# SolBin.net
KiCad netlist of a schematic drawn in Altium Designer
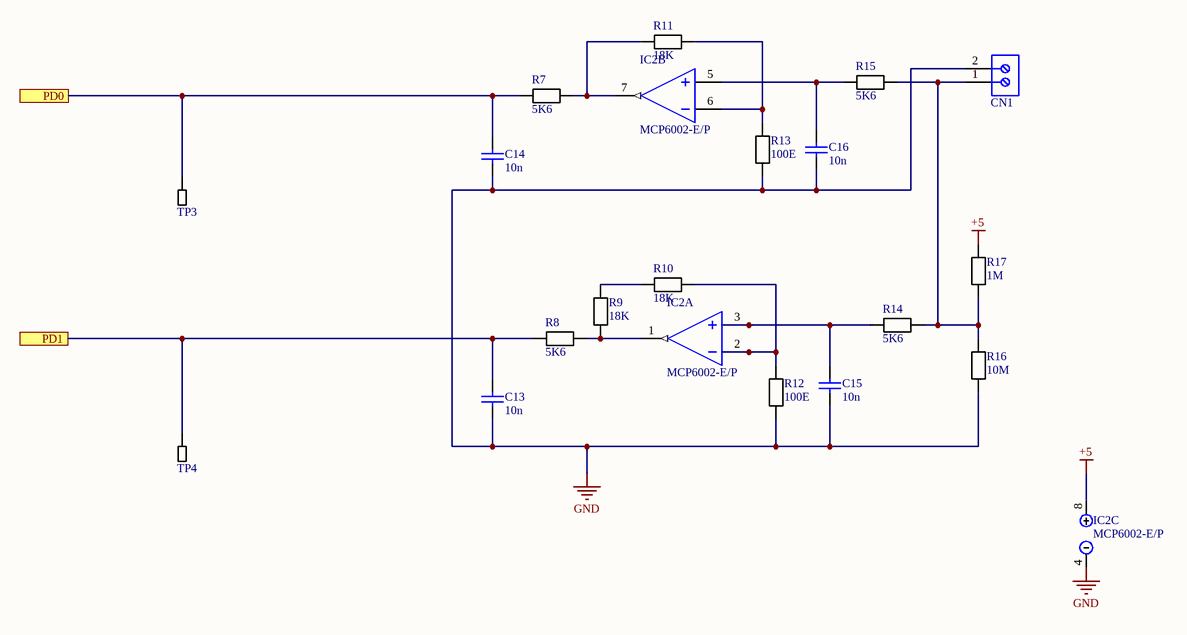
[diagram p0: SolBin.SchDoc]

(export (version "E")
  (design (tool "Eeschema 10.0.6"))
  (components
    (comp (ref "C13")
      (value "10n")
      (footprint "CAPA")
      (fields (field (name "PART NUMBER") "GRM1885C1H100JA01D") (field (name "MANUFACTURER") "Murata"))
      (libsource (lib "Schlib1") (part "Capasitor"))
    )
    (comp (ref "C14")
      (value "10n")
      (footprint "CAPA")
      (fields (field (name "PART NUMBER") "GRM1885C1H100JA01D") (field (name "MANUFACTURER") "Murata"))
      (libsource (lib "Schlib1") (part "Capasitor"))
    )
    (comp (ref "C15")
      (value "10n")
      (footprint "CAPA")
      (fields (field (name "PART NUMBER") "GRM1885C1H100JA01D") (field (name "MANUFACTURER") "Murata"))
      (libsource (lib "Schlib1") (part "Capasitor"))
    )
    (comp (ref "C16")
      (value "10n")
      (footprint "CAPA")
      (fields (field (name "PART NUMBER") "GRM1885C1H100JA01D") (field (name "MANUFACTURER") "Murata"))
      (libsource (lib "Schlib1") (part "Capasitor"))
    )
    (comp (ref "CN1")
      (value "1725656")
      (footprint "2 pinHeader")
      (fields (field (name "MANUFACTURER") "Phoenix Contact"))
      (libsource (lib "Schlib1") (part "2Pin-Header"))
    )
    (comp (ref "IC2")
      (value "MCP6002-E/P")
      (footprint "PDIP300-P8")
      (libsource (lib "Schlib1") (part "CMP-0187-00133-3"))
    )
    (comp (ref "R7")
      (value "5K6")
      (footprint "REST")
      (fields (field (name "MANUFACTURER") "Vishay Dale") (field (name "PART NUMBER") "CRCW08050000Z0EA"))
      (libsource (lib "Schlib1") (part "resistor"))
    )
    (comp (ref "R8")
      (value "5K6")
      (footprint "REST")
      (fields (field (name "MANUFACTURER") "Vishay Dale") (field (name "PART NUMBER") "CRCW08050000Z0EA"))
      (libsource (lib "Schlib1") (part "resistor"))
    )
    (comp (ref "R9")
      (value "18K")
      (footprint "REST")
      (fields (field (name "MANUFACTURER") "Vishay Dale") (field (name "PART NUMBER") "CRCW08050000Z0EA"))
      (libsource (lib "Schlib1") (part "resistor"))
    )
    (comp (ref "R10")
      (value "18K")
      (footprint "REST")
      (fields (field (name "MANUFACTURER") "Vishay Dale") (field (name "PART NUMBER") "CRCW08050000Z0EA"))
      (libsource (lib "Schlib1") (part "resistor"))
    )
    (comp (ref "R11")
      (value "18K")
      (footprint "REST")
      (fields (field (name "MANUFACTURER") "Vishay Dale") (field (name "PART NUMBER") "CRCW08050000Z0EA"))
      (libsource (lib "Schlib1") (part "resistor"))
    )
    (comp (ref "R12")
      (value "100E")
      (footprint "REST")
      (fields (field (name "MANUFACTURER") "Vishay Dale") (field (name "PART NUMBER") "CRCW08050000Z0EA"))
      (libsource (lib "Schlib1") (part "resistor"))
    )
    (comp (ref "R13")
      (value "100E")
      (footprint "REST")
      (fields (field (name "MANUFACTURER") "Vishay Dale") (field (name "PART NUMBER") "CRCW08050000Z0EA"))
      (libsource (lib "Schlib1") (part "resistor"))
    )
    (comp (ref "R14")
      (value "5K6")
      (footprint "REST")
      (fields (field (name "MANUFACTURER") "Vishay Dale") (field (name "PART NUMBER") "CRCW08050000Z0EA"))
      (libsource (lib "Schlib1") (part "resistor"))
    )
    (comp (ref "R15")
      (value "5K6")
      (footprint "REST")
      (fields (field (name "MANUFACTURER") "Vishay Dale") (field (name "PART NUMBER") "CRCW08050000Z0EA"))
      (libsource (lib "Schlib1") (part "resistor"))
    )
    (comp (ref "R16")
      (value "10M")
      (footprint "REST")
      (fields (field (name "MANUFACTURER") "Vishay Dale") (field (name "PART NUMBER") "CRCW08050000Z0EA"))
      (libsource (lib "Schlib1") (part "resistor"))
    )
    (comp (ref "R17")
      (value "1M")
      (footprint "REST")
      (fields (field (name "MANUFACTURER") "Vishay Dale") (field (name "PART NUMBER") "CRCW08050000Z0EA"))
      (libsource (lib "Schlib1") (part "resistor"))
    )
    (comp (ref "TP3")
      (value "TP")
      (footprint "TP")
      (fields (field (name "PART NUMBER") "GRM1885C1H100JA01D") (field (name "MANUFACTURER") "Murata"))
      (libsource (lib "Schlib1") (part "TP"))
    )
    (comp (ref "TP4")
      (value "TP")
      (footprint "TP")
      (fields (field (name "PART NUMBER") "GRM1885C1H100JA01D") (field (name "MANUFACTURER") "Murata"))
      (libsource (lib "Schlib1") (part "TP"))
    )
  )
  (nets
    (net (code "1") (name "+5") (class "Default")
      (node (ref "IC2") (pin "8") (pinfunction "1_8") (pintype "passive"))
      (node (ref "R17") (pin "2") (pinfunction "2_2") (pintype "passive"))
    )
    (net (code "2") (name "/PD0") (class "Default")
      (node (ref "C14") (pin "2") (pinfunction "2_2") (pintype "passive"))
      (node (ref "R7") (pin "1") (pinfunction "1_1") (pintype "passive"))
      (node (ref "TP3") (pin "1") (pinfunction "1_1") (pintype "passive"))
    )
    (net (code "3") (name "/PD1") (class "Default")
      (node (ref "C13") (pin "2") (pinfunction "2_2") (pintype "passive"))
      (node (ref "R8") (pin "1") (pinfunction "1_1") (pintype "passive"))
      (node (ref "TP4") (pin "1") (pinfunction "1_1") (pintype "passive"))
    )
    (net (code "4") (name "GND") (class "Default")
      (node (ref "C13") (pin "1") (pinfunction "1_1") (pintype "passive"))
      (node (ref "C14") (pin "1") (pinfunction "1_1") (pintype "passive"))
      (node (ref "C15") (pin "1") (pinfunction "1_1") (pintype "passive"))
      (node (ref "C16") (pin "1") (pinfunction "1_1") (pintype "passive"))
      (node (ref "CN1") (pin "2") (pinfunction "2_2") (pintype "passive"))
      (node (ref "IC2") (pin "4") (pinfunction "1_4") (pintype "passive"))
      (node (ref "R12") (pin "1") (pinfunction "1_1") (pintype "passive"))
      (node (ref "R13") (pin "1") (pinfunction "1_1") (pintype "passive"))
      (node (ref "R16") (pin "1") (pinfunction "1_1") (pintype "passive"))
    )
    (net (code "5") (name "Net-(CN1-Pad1)") (class "Default")
      (node (ref "CN1") (pin "1") (pinfunction "1_1") (pintype "passive"))
      (node (ref "R14") (pin "2") (pinfunction "2_2") (pintype "passive"))
      (node (ref "R15") (pin "2") (pinfunction "2_2") (pintype "passive"))
      (node (ref "R16") (pin "2") (pinfunction "2_2") (pintype "passive"))
      (node (ref "R17") (pin "1") (pinfunction "1_1") (pintype "passive"))
    )
    (net (code "6") (name "Net-(IC2A-VINA+)") (class "Default")
      (node (ref "C15") (pin "2") (pinfunction "2_2") (pintype "passive"))
      (node (ref "IC2") (pin "3") (pinfunction "VINA+_3") (pintype "passive"))
      (node (ref "R14") (pin "1") (pinfunction "1_1") (pintype "passive"))
    )
    (net (code "7") (name "Net-(IC2A-VINA-)") (class "Default")
      (node (ref "IC2") (pin "2") (pinfunction "VINA-_2") (pintype "passive"))
      (node (ref "R10") (pin "2") (pinfunction "2_2") (pintype "passive"))
      (node (ref "R12") (pin "2") (pinfunction "2_2") (pintype "passive"))
    )
    (net (code "8") (name "Net-(IC2A-VOUTA)") (class "Default")
      (node (ref "IC2") (pin "1") (pinfunction "VOUTA_1") (pintype "output"))
      (node (ref "R8") (pin "2") (pinfunction "2_2") (pintype "passive"))
      (node (ref "R9") (pin "1") (pinfunction "1_1") (pintype "passive"))
    )
    (net (code "9") (name "Net-(IC2B-VINB+)") (class "Default")
      (node (ref "C16") (pin "2") (pinfunction "2_2") (pintype "passive"))
      (node (ref "IC2") (pin "5") (pinfunction "VINB+_5") (pintype "passive"))
      (node (ref "R15") (pin "1") (pinfunction "1_1") (pintype "passive"))
    )
    (net (code "10") (name "Net-(IC2B-VINB-)") (class "Default")
      (node (ref "IC2") (pin "6") (pinfunction "VINB-_6") (pintype "passive"))
      (node (ref "R11") (pin "2") (pinfunction "2_2") (pintype "passive"))
      (node (ref "R13") (pin "2") (pinfunction "2_2") (pintype "passive"))
    )
    (net (code "11") (name "Net-(IC2B-VOUTB)") (class "Default")
      (node (ref "IC2") (pin "7") (pinfunction "VOUTB_7") (pintype "output"))
      (node (ref "R11") (pin "1") (pinfunction "1_1") (pintype "passive"))
      (node (ref "R7") (pin "2") (pinfunction "2_2") (pintype "passive"))
    )
    (net (code "12") (name "Net-(R10-Pad1)") (class "Default")
      (node (ref "R10") (pin "1") (pinfunction "1_1") (pintype "passive"))
      (node (ref "R9") (pin "2") (pinfunction "2_2") (pintype "passive"))
    )
  )
)
